# DST800_NMEA2k-CAN_Indicator.net
KiCad netlist of a schematic drawn in Altium Designer
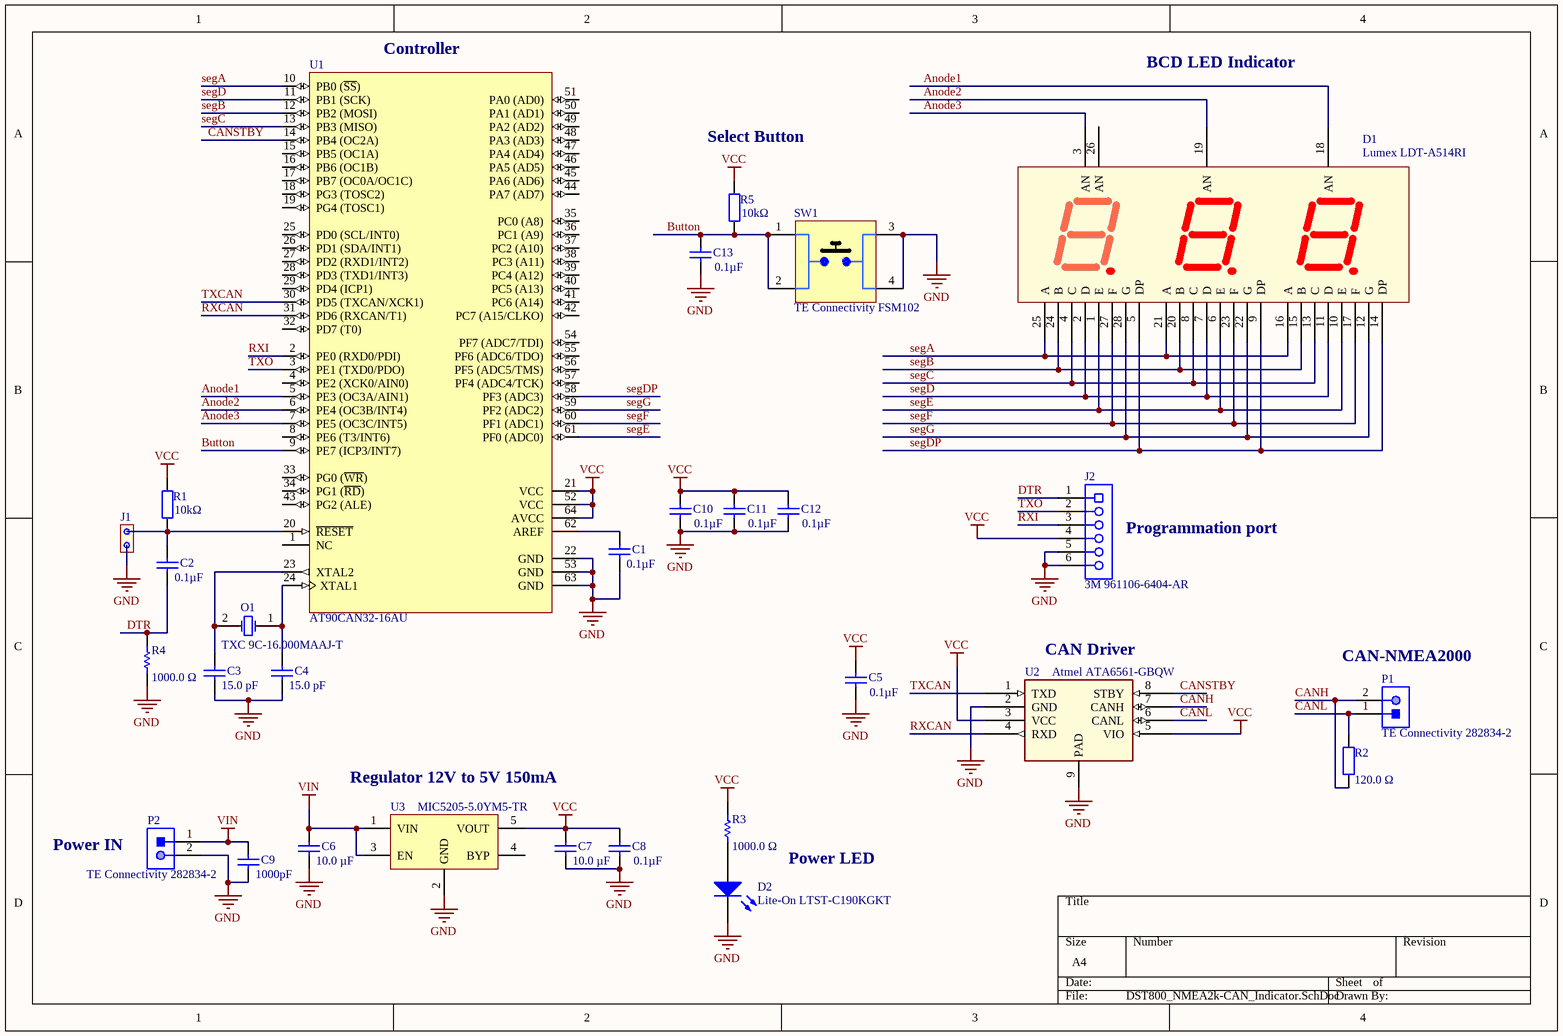
[diagram p0: DST800_NMEA2k-CAN_Indicator.SchDoc]

(export (version "E")
  (design (tool "Eeschema 10.0.6"))
  (components
    (comp (ref "C1")
      (value "Cap")
      (footprint "PCB-mhhqftc5ilnrg4qi8ds6-1")
      (description "CAP CER 0.1UF 50V X7R 0603")
      (fields
        (field (name "CAPACITANCE") "0.1µF")
        (field (name "MANUFACTURER") "Samsung Electro-Mechanics")
        (field (name "VENDOR PART NUMBER") "1276-1000-1-ND")
      )
      (libsource (lib "CommunityVault") (part "CMP-1af8d38ac64bc53f-5"))
    )
    (comp (ref "C2")
      (value "Cap")
      (footprint "PCB-mhhqftc5ilnrg4qi8ds6-1")
      (description "CAP CER 0.1UF 50V X7R 0603")
      (fields
        (field (name "CAPACITANCE") "0.1µF")
        (field (name "MANUFACTURER") "Samsung Electro-Mechanics")
        (field (name "VENDOR PART NUMBER") "1276-1000-1-ND")
      )
      (libsource (lib "CommunityVault") (part "CMP-1af8d38ac64bc53f-5"))
    )
    (comp (ref "C3")
      (value "Cap")
      (footprint "PCB-69ec8bfnjhyebnpbrrfx-1")
      (description "Multilayer Ceramic Capacitor, C Series, 15 pF, - 5%, C0G / NP0, 50 V, 0603 [1608 Metric]")
      (fields (field (name "CAPACITANCE") "15.0 pF"))
      (libsource (lib "CommunityVault") (part "CMP-57259fa49f8088e2-2"))
    )
    (comp (ref "C4")
      (value "Cap")
      (footprint "PCB-69ec8bfnjhyebnpbrrfx-1")
      (description "Multilayer Ceramic Capacitor, C Series, 15 pF, - 5%, C0G / NP0, 50 V, 0603 [1608 Metric]")
      (fields (field (name "CAPACITANCE") "15.0 pF"))
      (libsource (lib "CommunityVault") (part "CMP-57259fa49f8088e2-2"))
    )
    (comp (ref "C5")
      (value "Cap")
      (footprint "PCB-mhhqftc5ilnrg4qi8ds6-1")
      (description "CAP CER 0.1UF 50V X7R 0603")
      (fields
        (field (name "CAPACITANCE") "0.1µF")
        (field (name "MANUFACTURER") "Samsung Electro-Mechanics")
        (field (name "VENDOR PART NUMBER") "1276-1000-1-ND")
      )
      (libsource (lib "CommunityVault") (part "CMP-1af8d38ac64bc53f-5"))
    )
    (comp (ref "C6")
      (value "Cap")
      (footprint "PCB-j0jk5xr8qbnaskonccg4-1")
      (description "C Series 1210 10 uF 25 V ±10 % Tolerance X7R SMT Multilayer Ceramic Capacitor")
      (fields (field (name "CAPACITANCE") "10.0 µF"))
      (libsource (lib "CommunityVault") (part "CMP-2bdce35de069f41b-1"))
    )
    (comp (ref "C7")
      (value "Cap")
      (footprint "PCB-j0jk5xr8qbnaskonccg4-1")
      (description "C Series 1210 10 uF 25 V ±10 % Tolerance X7R SMT Multilayer Ceramic Capacitor")
      (fields (field (name "CAPACITANCE") "10.0 µF"))
      (libsource (lib "CommunityVault") (part "CMP-2bdce35de069f41b-1"))
    )
    (comp (ref "C8")
      (value "Cap")
      (footprint "PCB-mhhqftc5ilnrg4qi8ds6-1")
      (description "CAP CER 0.1UF 50V X7R 0603")
      (fields
        (field (name "CAPACITANCE") "0.1µF")
        (field (name "MANUFACTURER") "Samsung Electro-Mechanics")
        (field (name "VENDOR PART NUMBER") "1276-1000-1-ND")
      )
      (libsource (lib "CommunityVault") (part "CMP-1af8d38ac64bc53f-5"))
    )
    (comp (ref "C9")
      (value "AVX Interconnect / Elco 06031C102MAT2A")
      (footprint "CAPC1608X90X35LL15T15")
      (description "CAP CER 1000PF 100V 20% X7R 0603")
      (fields
        (field (name "MANUFACTURER PART NUMBER") "06031C102MAT2A")
        (field (name "CAPACITANCE") "1000pF")
      )
      (libsource (lib "CommunityVault") (part "CMP-126202-2"))
    )
    (comp (ref "C10")
      (value "Cap")
      (footprint "PCB-mhhqftc5ilnrg4qi8ds6-1")
      (description "CAP CER 0.1UF 50V X7R 0603")
      (fields
        (field (name "CAPACITANCE") "0.1µF")
        (field (name "MANUFACTURER") "Samsung Electro-Mechanics")
        (field (name "VENDOR PART NUMBER") "1276-1000-1-ND")
      )
      (libsource (lib "CommunityVault") (part "CMP-1af8d38ac64bc53f-5"))
    )
    (comp (ref "C11")
      (value "Cap")
      (footprint "PCB-mhhqftc5ilnrg4qi8ds6-1")
      (description "CAP CER 0.1UF 50V X7R 0603")
      (fields
        (field (name "CAPACITANCE") "0.1µF")
        (field (name "MANUFACTURER") "Samsung Electro-Mechanics")
        (field (name "VENDOR PART NUMBER") "1276-1000-1-ND")
      )
      (libsource (lib "CommunityVault") (part "CMP-1af8d38ac64bc53f-5"))
    )
    (comp (ref "C12")
      (value "Cap")
      (footprint "PCB-mhhqftc5ilnrg4qi8ds6-1")
      (description "CAP CER 0.1UF 50V X7R 0603")
      (fields
        (field (name "CAPACITANCE") "0.1µF")
        (field (name "MANUFACTURER") "Samsung Electro-Mechanics")
        (field (name "VENDOR PART NUMBER") "1276-1000-1-ND")
      )
      (libsource (lib "CommunityVault") (part "CMP-1af8d38ac64bc53f-5"))
    )
    (comp (ref "C13")
      (value "Cap")
      (footprint "PCB-mhhqftc5ilnrg4qi8ds6-1")
      (description "CAP CER 0.1UF 50V X7R 0603")
      (fields
        (field (name "CAPACITANCE") "0.1µF")
        (field (name "MANUFACTURER") "Samsung Electro-Mechanics")
        (field (name "VENDOR PART NUMBER") "1276-1000-1-ND")
      )
      (libsource (lib "CommunityVault") (part "CMP-1af8d38ac64bc53f-5"))
    )
    (comp (ref "D1")
      (value "Lumex LDT-A514RI")
      (footprint "LDTA514RI")
      (description "Display, 7-Segment; 3900 mucd (Typ.) @ 10 mA; 635 nm (Typ.); 0.56 in.; -40 degC")
      (fields (field (name "MANUFACTURER PART NUMBER") "LDT-A514RI"))
      (libsource (lib "FavoritesLibrary") (part "LDTA514RI"))
    )
    (comp (ref "D2")
      (value "Lite-On LTST-C190KGKT")
      (footprint "PCB-eapfwhp0rnksgujf96h3-1")
      (description "LED; SMD; 0603; green; 18-71mcd; 1.6x0.8x0.8mm; 130°; 1.9÷2.4V; 20mA")
      (fields (field (name "MANUFACTURER PART NUMBER") "LTST-C190KGKT"))
      (libsource (lib "CommunityVault") (part "SYM-e1642866a00b3ea3-1"))
    )
    (comp (ref "J1")
      (value "TE Connectivity 5-146281-2")
      (footprint "PCB-angfy19quc8nc8nc7d0m-1")
      (description "Header; Breakaway; 0.100 in.; PC Board; Single; 2; 0.025 in.; 0.12 in.; 3 A")
      (fields (field (name "MANUFACTURER PART NUMBER") "5-146281-2"))
      (libsource (lib "CommunityVault") (part "SYM-39c9f206a0b6e60e-3"))
    )
    (comp (ref "J2")
      (value "3M 961106-6404-AR")
      (footprint "PCB-660833-1")
      (description "CONN HEADER VERT SGL 6POS GOLD")
      (fields (field (name "MANUFACTURER PART NUMBER") "961106-6404-AR"))
      (libsource (lib "CommunityVault") (part "SYM-660833-1"))
    )
    (comp (ref "O1")
      (value "TXC 9C-16.000MAAJ-T")
      (footprint "PCB-3qvzojcyidn2gltqqmbl-1")
      (description "Crystal 16MHz ?30ppm (Tol) ?30ppm (Stability) 18pF FUND 30Ohm 2-Pin HC-49/S SMD T/R")
      (fields (field (name "MANUFACTURER PART NUMBER") "9C-16.000MAAJ-T"))
      (libsource (lib "CommunityVault") (part "SYM-df271731c43900e0-2"))
    )
    (comp (ref "P1")
      (value "TE Connectivity 282834-2")
      (footprint "PCB-0kdx5sneyudsmu18l6zv-1")
      (description "Connector, Terminal Block; Wire Receptacle; 2 Pos.; 16-30 AWG; 0.197 in. CL; Sid")
      (libsource (lib "") (part "SYM-4e52859dc8429195-1_1"))
    )
    (comp (ref "P2")
      (value "TE Connectivity 282834-2")
      (footprint "PCB-0kdx5sneyudsmu18l6zv-1")
      (description "Connector, Terminal Block; Wire Receptacle; 2 Pos.; 16-30 AWG; 0.197 in. CL; Sid")
      (libsource (lib "CommunityVault") (part "SYM-4e52859dc8429195-1"))
    )
    (comp (ref "R1")
      (value "Res2")
      (footprint "RESC1608X55X30NL15T15")
      (description "Resistor; Thick Film; Res 10 Kilohms; Pwr-Rtg 0.1 W; Tol 1%; SMT; 0603")
      (fields (field (name "MANUFACTURER PART NUMBER") "CRG0603F10K") (field (name "RESISTANCE") "10kΩ"))
      (libsource (lib "CommunityVault") (part "CMP-584891b72cc4878f-2"))
    )
    (comp (ref "R2")
      (value "Vishay Dale CRCW1206120RJNEA")
      (footprint "RESC3216X60X45LL10T20")
      (description "RES SMD 120 OHM 5% 1/4W 1206")
      (fields
        (field (name "RESISTANCE") "120.0 Ω")
        (field (name "MANUFACTURER PART NUMBER") "CRCW1206120RJNEA")
      )
      (libsource (lib "CommunityVault") (part "CMP-1858100-4"))
    )
    (comp (ref "R3")
      (value "Panasonic ERA-3YEB102V")
      (footprint "RESC1608X55X30NL20T20")
      (description "Metal Film Resistors 1K    OHM  .1% 25PPM")
      (fields (field (name "RESISTANCE") "1000.0 Ω") (field (name "MANUFACTURER PART NUMBER") "ERA-3YEB102V"))
      (libsource (lib "CommunityVault") (part "CMP-3717598-2"))
    )
    (comp (ref "R4")
      (value "Panasonic ERA-3YEB102V")
      (footprint "RESC1608X55X30NL20T20")
      (description "Metal Film Resistors 1K    OHM  .1% 25PPM")
      (fields (field (name "RESISTANCE") "1000.0 Ω") (field (name "MANUFACTURER PART NUMBER") "ERA-3YEB102V"))
      (libsource (lib "CommunityVault") (part "CMP-3717598-2"))
    )
    (comp (ref "R5")
      (value "Res2")
      (footprint "RESC1608X55X30NL15T15")
      (description "Resistor; Thick Film; Res 10 Kilohms; Pwr-Rtg 0.1 W; Tol 1%; SMT; 0603")
      (fields (field (name "MANUFACTURER PART NUMBER") "CRG0603F10K") (field (name "RESISTANCE") "10kΩ"))
      (libsource (lib "CommunityVault") (part "CMP-584891b72cc4878f-2"))
    )
    (comp (ref "SW1")
      (value "TE Connectivity FSM102")
      (footprint "PCB-8ps4wla3pj92cxv2yuvu-1")
      (description "Momentary Tactile SPST Thru-Hole")
      (fields (field (name "MANUFACTURER PART NUMBER") "FSM102"))
      (libsource (lib "CommunityVault") (part "SYM-43e488b0e8c29c23-1"))
    )
    (comp (ref "U1")
      (value "AT90CAN32-16AU")
      (footprint "64A_L")
      (libsource (lib "CommunityVault") (part "MC-8B-AT90CAN32-SQ64"))
    )
    (comp (ref "U2")
      (value "Atmel ATA6561-GBQW")
      (footprint "PCBComponent_1")
      (description "CAN 5Mbps Normal/Silent/Standby 5V Automotive 8-Pin VDFN EP T/R")
      (fields (field (name "MANUFACTURER PART NUMBER") "ATA6561-GBQW"))
      (libsource (lib "CommunityVault") (part "SYM-9a565056add04591-1"))
    )
    (comp (ref "U3")
      (value "MIC5205-5.0YM5-TR")
      (footprint "SOT-23-5_N")
      (description "Microchip MIC5205 Series 5 V Fixed Output 150 mA SMT Low-Noise LDO Regulator - SOT-23-5")
      (libsource (lib "CommunityVault") (part "MIC5205-5.0YM5-TR"))
    )
  )
  (nets
    (net (code "1") (name "/Anode1") (class "Default")
      (node (ref "D1") (pin "18") (pinfunction "AN_18") (pintype "passive"))
      (node (ref "U1") (pin "5") (pinfunction "PE3_(OC3A/AIN1)_5") (pintype "bidirectional"))
    )
    (net (code "2") (name "/Anode2") (class "Default")
      (node (ref "D1") (pin "19") (pinfunction "AN_19") (pintype "passive"))
      (node (ref "U1") (pin "6") (pinfunction "PE4_(OC3B/INT4)_6") (pintype "bidirectional"))
    )
    (net (code "3") (name "/Anode3") (class "Default")
      (node (ref "D1") (pin "3") (pinfunction "AN_3") (pintype "passive"))
      (node (ref "U1") (pin "7") (pinfunction "PE5_(OC3C/INT5)_7") (pintype "bidirectional"))
    )
    (net (code "4") (name "/Button") (class "Default")
      (node (ref "C13") (pin "2") (pinfunction "2_2") (pintype "passive"))
      (node (ref "R5") (pin "1") (pinfunction "1_1") (pintype "passive"))
      (node (ref "SW1") (pin "1") (pinfunction "1_1") (pintype "passive"))
      (node (ref "SW1") (pin "2") (pinfunction "2_2") (pintype "passive"))
      (node (ref "U1") (pin "9") (pinfunction "PE7_(ICP3/INT7)_9") (pintype "bidirectional"))
    )
    (net (code "5") (name "/CANH") (class "Default")
      (node (ref "P1") (pin "2") (pinfunction "2_2") (pintype "passive"))
      (node (ref "R2") (pin "1") (pinfunction "1_1") (pintype "passive"))
      (node (ref "U2") (pin "7") (pinfunction "CANH_7") (pintype "bidirectional"))
    )
    (net (code "6") (name "/CANL") (class "Default")
      (node (ref "P1") (pin "1") (pinfunction "1_1") (pintype "passive"))
      (node (ref "R2") (pin "2") (pinfunction "2_2") (pintype "passive"))
      (node (ref "U2") (pin "6") (pinfunction "CANL_6") (pintype "bidirectional"))
    )
    (net (code "7") (name "/CANSTBY") (class "Default")
      (node (ref "U1") (pin "14") (pinfunction "PB4_(OC2A)_14") (pintype "bidirectional"))
      (node (ref "U2") (pin "8") (pinfunction "STBY_8") (pintype "input"))
    )
    (net (code "8") (name "/DTR") (class "Default")
      (node (ref "C2") (pin "1") (pinfunction "1_1") (pintype "passive"))
      (node (ref "J2") (pin "1") (pinfunction "1_1") (pintype "passive"))
      (node (ref "R4") (pin "2") (pinfunction "2_2") (pintype "passive"))
    )
    (net (code "9") (name "/RXCAN") (class "Default")
      (node (ref "U1") (pin "31") (pinfunction "PD6_(RXCAN/T1)_31") (pintype "bidirectional"))
      (node (ref "U2") (pin "4") (pinfunction "RXD_4") (pintype "output"))
    )
    (net (code "10") (name "/RXI") (class "Default")
      (node (ref "J2") (pin "3") (pinfunction "3_3") (pintype "passive"))
      (node (ref "U1") (pin "2") (pinfunction "PE0_(RXD0/PDI)_2") (pintype "bidirectional"))
    )
    (net (code "11") (name "/TXCAN") (class "Default")
      (node (ref "U1") (pin "30") (pinfunction "PD5_(TXCAN/XCK1)_30") (pintype "bidirectional"))
      (node (ref "U2") (pin "1") (pinfunction "TXD_1") (pintype "input"))
    )
    (net (code "12") (name "/TXO") (class "Default")
      (node (ref "J2") (pin "2") (pinfunction "2_2") (pintype "passive"))
      (node (ref "U1") (pin "3") (pinfunction "PE1_(TXD0/PDO)_3") (pintype "bidirectional"))
    )
    (net (code "13") (name "/segA") (class "Default")
      (node (ref "D1") (pin "16") (pinfunction "A_16") (pintype "passive"))
      (node (ref "D1") (pin "21") (pinfunction "A_21") (pintype "passive"))
      (node (ref "D1") (pin "25") (pinfunction "A_25") (pintype "passive"))
      (node (ref "U1") (pin "10") (pinfunction "PB0_(~{SS})_10") (pintype "bidirectional"))
    )
    (net (code "14") (name "/segB") (class "Default")
      (node (ref "D1") (pin "15") (pinfunction "B_15") (pintype "passive"))
      (node (ref "D1") (pin "20") (pinfunction "B_20") (pintype "passive"))
      (node (ref "D1") (pin "24") (pinfunction "B_24") (pintype "passive"))
      (node (ref "U1") (pin "12") (pinfunction "PB2_(MOSI)_12") (pintype "bidirectional"))
    )
    (net (code "15") (name "/segC") (class "Default")
      (node (ref "D1") (pin "13") (pinfunction "C_13") (pintype "passive"))
      (node (ref "D1") (pin "4") (pinfunction "C_4") (pintype "passive"))
      (node (ref "D1") (pin "8") (pinfunction "C_8") (pintype "passive"))
      (node (ref "U1") (pin "13") (pinfunction "PB3_(MISO)_13") (pintype "bidirectional"))
    )
    (net (code "16") (name "/segD") (class "Default")
      (node (ref "D1") (pin "11") (pinfunction "D_11") (pintype "passive"))
      (node (ref "D1") (pin "2") (pinfunction "D_2") (pintype "passive"))
      (node (ref "D1") (pin "7") (pinfunction "D_7") (pintype "passive"))
      (node (ref "U1") (pin "11") (pinfunction "PB1_(SCK)_11") (pintype "bidirectional"))
    )
    (net (code "17") (name "/segDP") (class "Default")
      (node (ref "D1") (pin "14") (pinfunction "DP_14") (pintype "passive"))
      (node (ref "D1") (pin "5") (pinfunction "DP_5") (pintype "passive"))
      (node (ref "D1") (pin "9") (pinfunction "DP_9") (pintype "passive"))
      (node (ref "U1") (pin "58") (pinfunction "PF3_(ADC3)_58") (pintype "bidirectional"))
    )
    (net (code "18") (name "/segE") (class "Default")
      (node (ref "D1") (pin "1") (pinfunction "E_1") (pintype "passive"))
      (node (ref "D1") (pin "10") (pinfunction "E_10") (pintype "passive"))
      (node (ref "D1") (pin "6") (pinfunction "E_6") (pintype "passive"))
      (node (ref "U1") (pin "61") (pinfunction "PF0_(ADC0)_61") (pintype "bidirectional"))
    )
    (net (code "19") (name "/segF") (class "Default")
      (node (ref "D1") (pin "17") (pinfunction "F_17") (pintype "passive"))
      (node (ref "D1") (pin "23") (pinfunction "F_23") (pintype "passive"))
      (node (ref "D1") (pin "27") (pinfunction "F_27") (pintype "passive"))
      (node (ref "U1") (pin "60") (pinfunction "PF1_(ADC1)_60") (pintype "bidirectional"))
    )
    (net (code "20") (name "/segG") (class "Default")
      (node (ref "D1") (pin "12") (pinfunction "G_12") (pintype "passive"))
      (node (ref "D1") (pin "22") (pinfunction "G_22") (pintype "passive"))
      (node (ref "D1") (pin "28") (pinfunction "G_28") (pintype "passive"))
      (node (ref "U1") (pin "59") (pinfunction "PF2_(ADC2)_59") (pintype "bidirectional"))
    )
    (net (code "21") (name "GND") (class "Default")
      (node (ref "C1") (pin "1") (pinfunction "1_1") (pintype "passive"))
      (node (ref "C10") (pin "1") (pinfunction "1_1") (pintype "passive"))
      (node (ref "C11") (pin "1") (pinfunction "1_1") (pintype "passive"))
      (node (ref "C12") (pin "1") (pinfunction "1_1") (pintype "passive"))
      (node (ref "C13") (pin "1") (pinfunction "1_1") (pintype "passive"))
      (node (ref "C3") (pin "1") (pinfunction "1_1") (pintype "passive"))
      (node (ref "C4") (pin "1") (pinfunction "1_1") (pintype "passive"))
      (node (ref "C5") (pin "1") (pinfunction "1_1") (pintype "passive"))
      (node (ref "C6") (pin "1") (pinfunction "1_1") (pintype "passive"))
      (node (ref "C7") (pin "1") (pinfunction "1_1") (pintype "passive"))
      (node (ref "C8") (pin "1") (pinfunction "1_1") (pintype "passive"))
      (node (ref "C9") (pin "1") (pinfunction "1_1") (pintype "passive"))
      (node (ref "D2") (pin "2") (pinfunction "K_2") (pintype "passive"))
      (node (ref "J1") (pin "2") (pinfunction "2_2") (pintype "passive"))
      (node (ref "J2") (pin "5") (pinfunction "5_5") (pintype "passive"))
      (node (ref "J2") (pin "6") (pinfunction "6_6") (pintype "passive"))
      (node (ref "P2") (pin "2") (pinfunction "2_2") (pintype "passive"))
      (node (ref "R4") (pin "1") (pinfunction "1_1") (pintype "passive"))
      (node (ref "SW1") (pin "3") (pinfunction "3_3") (pintype "passive"))
      (node (ref "SW1") (pin "4") (pinfunction "4_4") (pintype "passive"))
      (node (ref "U1") (pin "22") (pinfunction "GND_22") (pintype "power_in"))
      (node (ref "U1") (pin "53") (pinfunction "GND_53") (pintype "power_in"))
      (node (ref "U1") (pin "63") (pinfunction "GND_63") (pintype "power_in"))
      (node (ref "U2") (pin "2") (pinfunction "GND_2") (pintype "power_in"))
      (node (ref "U2") (pin "9") (pinfunction "PAD_9") (pintype "power_in"))
      (node (ref "U3") (pin "2") (pinfunction "GND_2") (pintype "passive"))
    )
    (net (code "22") (name "Net-(D2-A)") (class "Default")
      (node (ref "D2") (pin "1") (pinfunction "A_1") (pintype "passive"))
      (node (ref "R3") (pin "1") (pinfunction "1_1") (pintype "passive"))
    )
    (net (code "23") (name "Net-(O1-X1)") (class "Default")
      (node (ref "C4") (pin "2") (pinfunction "2_2") (pintype "passive"))
      (node (ref "O1") (pin "1") (pinfunction "X1_1") (pintype "passive"))
      (node (ref "U1") (pin "24") (pinfunction "XTAL1_24") (pintype "input"))
    )
    (net (code "24") (name "Net-(O1-X2)") (class "Default")
      (node (ref "C3") (pin "2") (pinfunction "2_2") (pintype "passive"))
      (node (ref "O1") (pin "2") (pinfunction "X2_2") (pintype "passive"))
      (node (ref "U1") (pin "23") (pinfunction "XTAL2_23") (pintype "output"))
    )
    (net (code "25") (name "Net-(U1-AREF)") (class "Default")
      (node (ref "C1") (pin "2") (pinfunction "2_2") (pintype "passive"))
      (node (ref "U1") (pin "62") (pinfunction "AREF_62") (pintype "power_in"))
    )
    (net (code "26") (name "Net-(U1-~{RESET})") (class "Default")
      (node (ref "C2") (pin "2") (pinfunction "2_2") (pintype "passive"))
      (node (ref "J1") (pin "1") (pinfunction "1_1") (pintype "passive"))
      (node (ref "R1") (pin "1") (pinfunction "1_1") (pintype "passive"))
      (node (ref "U1") (pin "20") (pinfunction "~{RESET}_20") (pintype "input"))
    )
    (net (code "27") (name "VCC") (class "Default")
      (node (ref "C10") (pin "2") (pinfunction "2_2") (pintype "passive"))
      (node (ref "C11") (pin "2") (pinfunction "2_2") (pintype "passive"))
      (node (ref "C12") (pin "2") (pinfunction "2_2") (pintype "passive"))
      (node (ref "C5") (pin "2") (pinfunction "2_2") (pintype "passive"))
      (node (ref "C7") (pin "2") (pinfunction "2_2") (pintype "passive"))
      (node (ref "C8") (pin "2") (pinfunction "2_2") (pintype "passive"))
      (node (ref "J2") (pin "4") (pinfunction "4_4") (pintype "passive"))
      (node (ref "R1") (pin "2") (pinfunction "2_2") (pintype "passive"))
      (node (ref "R3") (pin "2") (pinfunction "2_2") (pintype "passive"))
      (node (ref "R5") (pin "2") (pinfunction "2_2") (pintype "passive"))
      (node (ref "U1") (pin "21") (pinfunction "VCC_21") (pintype "power_in"))
      (node (ref "U1") (pin "52") (pinfunction "VCC_52") (pintype "power_in"))
      (node (ref "U1") (pin "64") (pinfunction "AVCC_64") (pintype "power_in"))
      (node (ref "U2") (pin "3") (pinfunction "VCC_3") (pintype "power_in"))
      (node (ref "U2") (pin "5") (pinfunction "VIO_5") (pintype "input"))
      (node (ref "U3") (pin "5") (pinfunction "VOUT_5") (pintype "passive"))
    )
    (net (code "28") (name "VIN") (class "Default")
      (node (ref "C6") (pin "2") (pinfunction "2_2") (pintype "passive"))
      (node (ref "C9") (pin "2") (pinfunction "2_2") (pintype "passive"))
      (node (ref "P2") (pin "1") (pinfunction "1_1") (pintype "passive"))
      (node (ref "U3") (pin "1") (pinfunction "VIN_1") (pintype "passive"))
      (node (ref "U3") (pin "3") (pinfunction "EN_3") (pintype "passive"))
    )
    (net (code "29") (name "unconnected-(D1-AN-Pad26)") (class "Default")
      (node (ref "D1") (pin "26") (pinfunction "AN_26") (pintype "passive"))
    )
    (net (code "30") (name "unconnected-(U1-NC-Pad1)") (class "Default")
      (node (ref "U1") (pin "1") (pinfunction "NC_1") (pintype "passive"))
    )
    (net (code "31") (name "unconnected-(U1-PA0_(AD0)-Pad51)") (class "Default")
      (node (ref "U1") (pin "51") (pinfunction "PA0_(AD0)_51") (pintype "bidirectional"))
    )
    (net (code "32") (name "unconnected-(U1-PA1_(AD1)-Pad50)") (class "Default")
      (node (ref "U1") (pin "50") (pinfunction "PA1_(AD1)_50") (pintype "bidirectional"))
    )
    (net (code "33") (name "unconnected-(U1-PA2_(AD2)-Pad49)") (class "Default")
      (node (ref "U1") (pin "49") (pinfunction "PA2_(AD2)_49") (pintype "bidirectional"))
    )
    (net (code "34") (name "unconnected-(U1-PA3_(AD3)-Pad48)") (class "Default")
      (node (ref "U1") (pin "48") (pinfunction "PA3_(AD3)_48") (pintype "bidirectional"))
    )
    (net (code "35") (name "unconnected-(U1-PA4_(AD4)-Pad47)") (class "Default")
      (node (ref "U1") (pin "47") (pinfunction "PA4_(AD4)_47") (pintype "bidirectional"))
    )
    (net (code "36") (name "unconnected-(U1-PA5_(AD5)-Pad46)") (class "Default")
      (node (ref "U1") (pin "46") (pinfunction "PA5_(AD5)_46") (pintype "bidirectional"))
    )
    (net (code "37") (name "unconnected-(U1-PA6_(AD6)-Pad45)") (class "Default")
      (node (ref "U1") (pin "45") (pinfunction "PA6_(AD6)_45") (pintype "bidirectional"))
    )
    (net (code "38") (name "unconnected-(U1-PA7_(AD7)-Pad44)") (class "Default")
      (node (ref "U1") (pin "44") (pinfunction "PA7_(AD7)_44") (pintype "bidirectional"))
    )
    (net (code "39") (name "unconnected-(U1-PB5_(OC1A)-Pad15)") (class "Default")
      (node (ref "U1") (pin "15") (pinfunction "PB5_(OC1A)_15") (pintype "bidirectional"))
    )
    (net (code "40") (name "unconnected-(U1-PB6_(OC1B)-Pad16)") (class "Default")
      (node (ref "U1") (pin "16") (pinfunction "PB6_(OC1B)_16") (pintype "bidirectional"))
    )
    (net (code "41") (name "unconnected-(U1-PB7_(OC0A{slash}OC1C)-Pad17)") (class "Default")
      (node (ref "U1") (pin "17") (pinfunction "PB7_(OC0A/OC1C)_17") (pintype "bidirectional"))
    )
    (net (code "42") (name "unconnected-(U1-PC0_(A8)-Pad35)") (class "Default")
      (node (ref "U1") (pin "35") (pinfunction "PC0_(A8)_35") (pintype "bidirectional"))
    )
    (net (code "43") (name "unconnected-(U1-PC1_(A9)-Pad36)") (class "Default")
      (node (ref "U1") (pin "36") (pinfunction "PC1_(A9)_36") (pintype "bidirectional"))
    )
    (net (code "44") (name "unconnected-(U1-PC2_(A10)-Pad37)") (class "Default")
      (node (ref "U1") (pin "37") (pinfunction "PC2_(A10)_37") (pintype "bidirectional"))
    )
    (net (code "45") (name "unconnected-(U1-PC3_(A11)-Pad38)") (class "Default")
      (node (ref "U1") (pin "38") (pinfunction "PC3_(A11)_38") (pintype "bidirectional"))
    )
    (net (code "46") (name "unconnected-(U1-PC4_(A12)-Pad39)") (class "Default")
      (node (ref "U1") (pin "39") (pinfunction "PC4_(A12)_39") (pintype "bidirectional"))
    )
    (net (code "47") (name "unconnected-(U1-PC5_(A13)-Pad40)") (class "Default")
      (node (ref "U1") (pin "40") (pinfunction "PC5_(A13)_40") (pintype "bidirectional"))
    )
    (net (code "48") (name "unconnected-(U1-PC6_(A14)-Pad41)") (class "Default")
      (node (ref "U1") (pin "41") (pinfunction "PC6_(A14)_41") (pintype "bidirectional"))
    )
    (net (code "49") (name "unconnected-(U1-PC7_(A15{slash}CLKO)-Pad42)") (class "Default")
      (node (ref "U1") (pin "42") (pinfunction "PC7_(A15/CLKO)_42") (pintype "bidirectional"))
    )
    (net (code "50") (name "unconnected-(U1-PD0_(SCL{slash}INT0)-Pad25)") (class "Default")
      (node (ref "U1") (pin "25") (pinfunction "PD0_(SCL/INT0)_25") (pintype "bidirectional"))
    )
    (net (code "51") (name "unconnected-(U1-PD1_(SDA{slash}INT1)-Pad26)") (class "Default")
      (node (ref "U1") (pin "26") (pinfunction "PD1_(SDA/INT1)_26") (pintype "bidirectional"))
    )
    (net (code "52") (name "unconnected-(U1-PD2_(RXD1{slash}INT2)-Pad27)") (class "Default")
      (node (ref "U1") (pin "27") (pinfunction "PD2_(RXD1/INT2)_27") (pintype "bidirectional"))
    )
    (net (code "53") (name "unconnected-(U1-PD3_(TXD1{slash}INT3)-Pad28)") (class "Default")
      (node (ref "U1") (pin "28") (pinfunction "PD3_(TXD1/INT3)_28") (pintype "bidirectional"))
    )
    (net (code "54") (name "unconnected-(U1-PD4_(ICP1)-Pad29)") (class "Default")
      (node (ref "U1") (pin "29") (pinfunction "PD4_(ICP1)_29") (pintype "bidirectional"))
    )
    (net (code "55") (name "unconnected-(U1-PD7_(T0)-Pad32)") (class "Default")
      (node (ref "U1") (pin "32") (pinfunction "PD7_(T0)_32") (pintype "bidirectional"))
    )
    (net (code "56") (name "unconnected-(U1-PE2_(XCK0{slash}AIN0)-Pad4)") (class "Default")
      (node (ref "U1") (pin "4") (pinfunction "PE2_(XCK0/AIN0)_4") (pintype "bidirectional"))
    )
    (net (code "57") (name "unconnected-(U1-PE6_(T3{slash}INT6)-Pad8)") (class "Default")
      (node (ref "U1") (pin "8") (pinfunction "PE6_(T3/INT6)_8") (pintype "bidirectional"))
    )
    (net (code "58") (name "unconnected-(U1-PF4_(ADC4{slash}TCK)-Pad57)") (class "Default")
      (node (ref "U1") (pin "57") (pinfunction "PF4_(ADC4/TCK)_57") (pintype "bidirectional"))
    )
    (net (code "59") (name "unconnected-(U1-PF5_(ADC5{slash}TMS)-Pad56)") (class "Default")
      (node (ref "U1") (pin "56") (pinfunction "PF5_(ADC5/TMS)_56") (pintype "bidirectional"))
    )
    (net (code "60") (name "unconnected-(U1-PF6_(ADC6{slash}TDO)-Pad55)") (class "Default")
      (node (ref "U1") (pin "55") (pinfunction "PF6_(ADC6/TDO)_55") (pintype "bidirectional"))
    )
    (net (code "61") (name "unconnected-(U1-PF7_(ADC7{slash}TDI)-Pad54)") (class "Default")
      (node (ref "U1") (pin "54") (pinfunction "PF7_(ADC7/TDI)_54") (pintype "bidirectional"))
    )
    (net (code "62") (name "unconnected-(U1-PG0_(~{WR})-Pad33)") (class "Default")
      (node (ref "U1") (pin "33") (pinfunction "PG0_(~{WR})_33") (pintype "bidirectional"))
    )
    (net (code "63") (name "unconnected-(U1-PG1_(~{RD})-Pad34)") (class "Default")
      (node (ref "U1") (pin "34") (pinfunction "PG1_(~{RD})_34") (pintype "bidirectional"))
    )
    (net (code "64") (name "unconnected-(U1-PG2_(ALE)-Pad43)") (class "Default")
      (node (ref "U1") (pin "43") (pinfunction "PG2_(ALE)_43") (pintype "bidirectional"))
    )
    (net (code "65") (name "unconnected-(U1-PG3_(TOSC2)-Pad18)") (class "Default")
      (node (ref "U1") (pin "18") (pinfunction "PG3_(TOSC2)_18") (pintype "bidirectional"))
    )
    (net (code "66") (name "unconnected-(U1-PG4_(TOSC1)-Pad19)") (class "Default")
      (node (ref "U1") (pin "19") (pinfunction "PG4_(TOSC1)_19") (pintype "bidirectional"))
    )
    (net (code "67") (name "unconnected-(U3-BYP-Pad4)") (class "Default")
      (node (ref "U3") (pin "4") (pinfunction "BYP_4") (pintype "passive"))
    )
  )
)
